# Brakeout_board_-_VEML7700.net
KiCad netlist of a schematic drawn in EAGLE
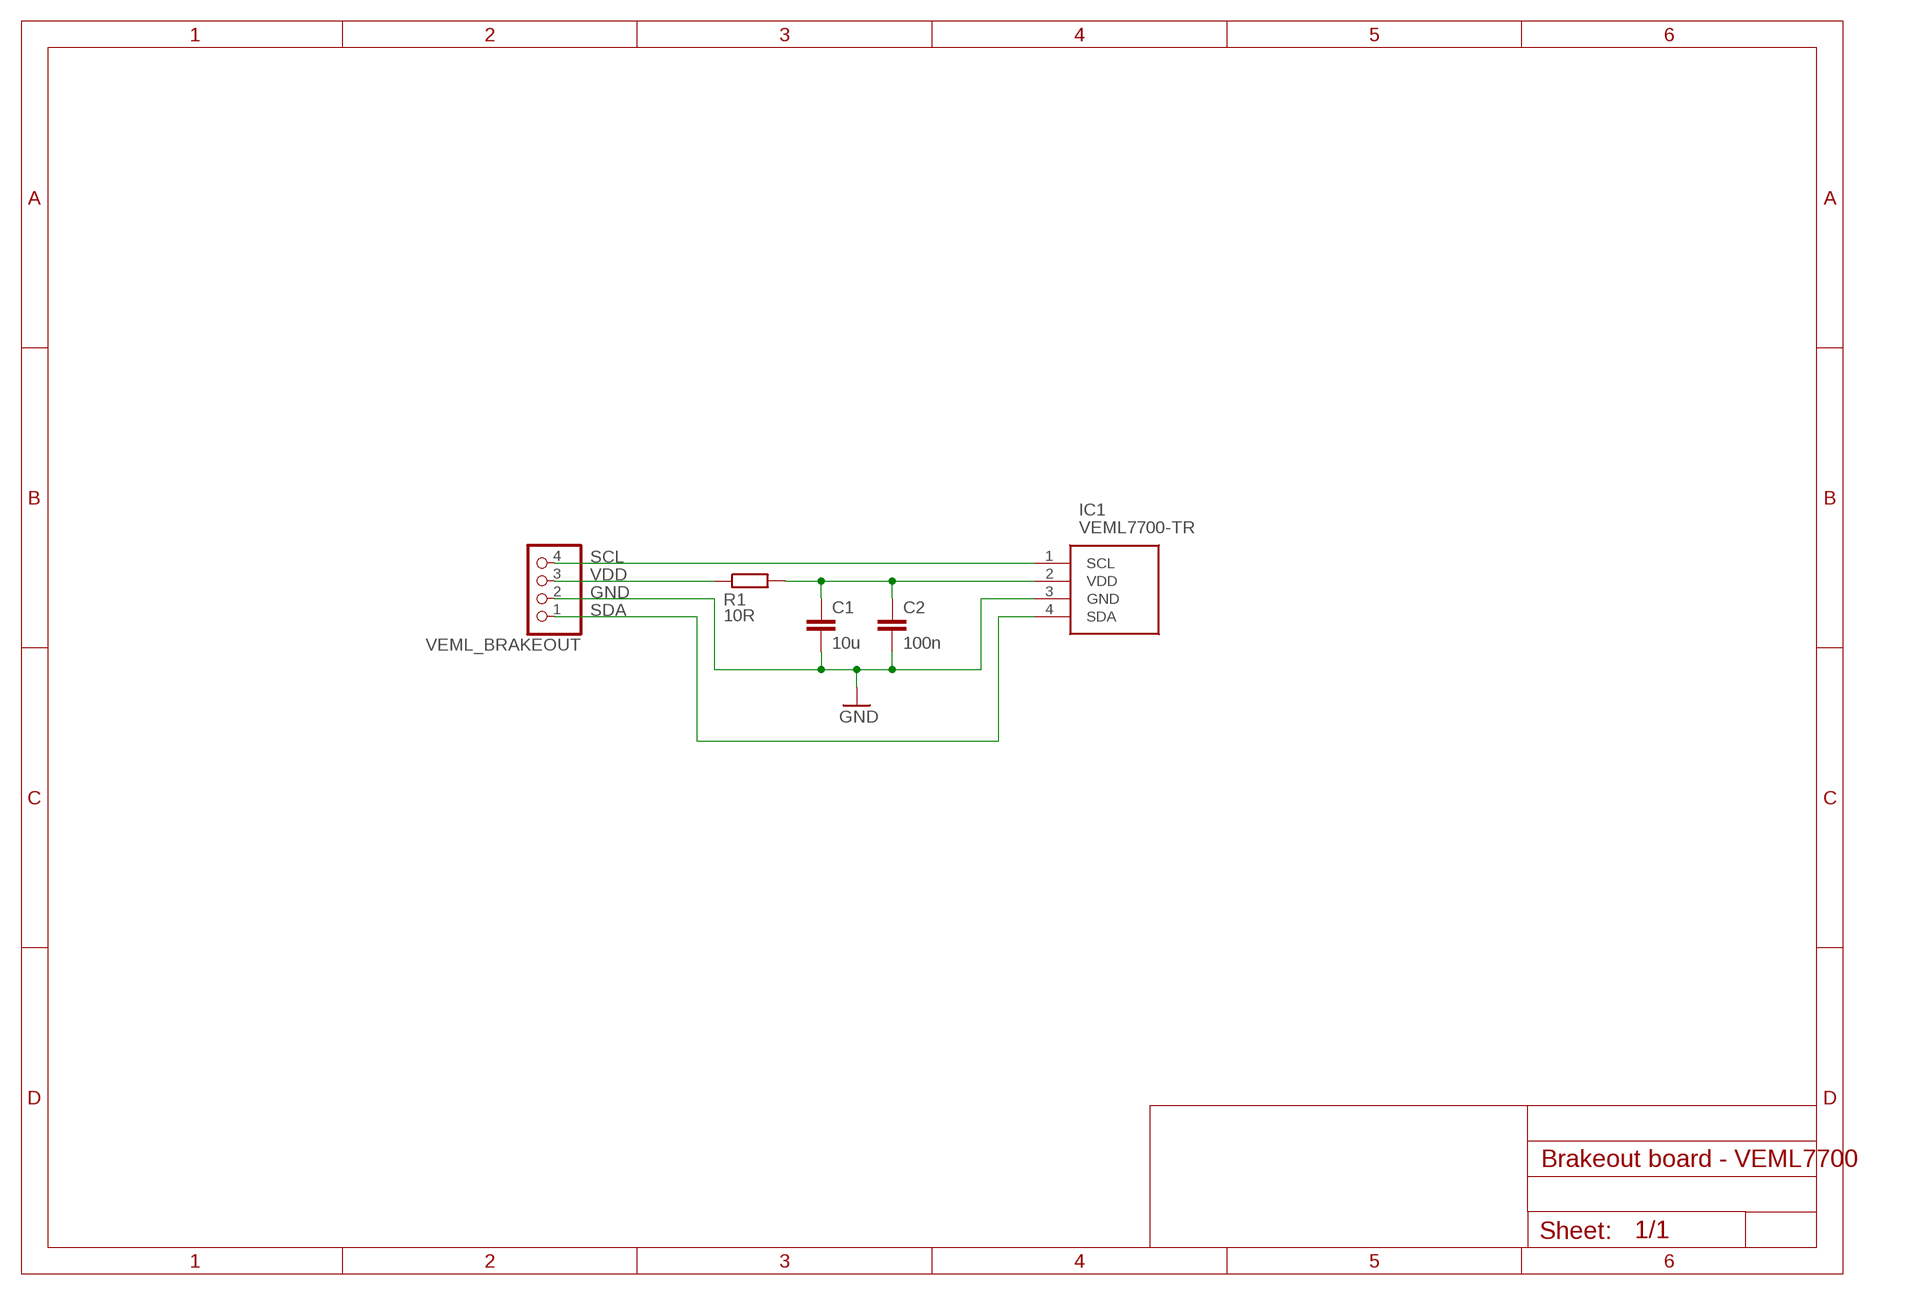
[diagram p0: schematic, sheet 1]

(export (version "E")
  (design (tool "Eeschema 10.0.6"))
  (components
    (comp (ref "C1")
      (value "10u")
      (footprint "eagle-import:C0603")
      (libsource (lib "eagle-import") (part "C-EUC0603"))
    )
    (comp (ref "C2")
      (value "100n")
      (footprint "eagle-import:C0603")
      (libsource (lib "eagle-import") (part "C-EUC0603"))
    )
    (comp (ref "IC1")
      (value "VEML7700-TR")
      (footprint "eagle-import:VEML7700")
      (fields (field (name "MOUSER_PART_NUMBER") "78-VEML7700-TR"))
      (libsource (lib "eagle-import") (part "VEML7700-TR"))
    )
    (comp (ref "R1")
      (value "10R")
      (footprint "eagle-import:R0603")
      (libsource (lib "eagle-import") (part "R-EU_R0603"))
    )
    (comp (ref "VEML_BRAKEOUT")
      (value "PINHD-1X4")
      (footprint "eagle-import:1X04")
      (libsource (lib "eagle-import") (part "PINHD-1X4"))
    )
  )
  (nets
    (net (code "1") (name "/SCL") (class "Default")
      (node (ref "IC1") (pin "1") (pinfunction "SCL_1") (pintype "bidirectional"))
      (node (ref "VEML_BRAKEOUT") (pin "4") (pinfunction "4_4") (pintype "passive"))
    )
    (net (code "2") (name "/SDA") (class "Default")
      (node (ref "IC1") (pin "4") (pinfunction "SDA_4") (pintype "bidirectional"))
      (node (ref "VEML_BRAKEOUT") (pin "1") (pinfunction "1_1") (pintype "passive"))
    )
    (net (code "3") (name "/VDD") (class "Default")
      (node (ref "R1") (pin "1") (pinfunction "1_1") (pintype "passive"))
      (node (ref "VEML_BRAKEOUT") (pin "3") (pinfunction "3_3") (pintype "passive"))
    )
    (net (code "4") (name "GND") (class "Default")
      (node (ref "C1") (pin "2") (pinfunction "2_2") (pintype "passive"))
      (node (ref "C2") (pin "2") (pinfunction "2_2") (pintype "passive"))
      (node (ref "IC1") (pin "3") (pinfunction "GND_3") (pintype "power_in"))
      (node (ref "VEML_BRAKEOUT") (pin "2") (pinfunction "2_2") (pintype "passive"))
    )
    (net (code "5") (name "Net-(IC1-VDD)") (class "Default")
      (node (ref "C1") (pin "1") (pinfunction "1_1") (pintype "passive"))
      (node (ref "C2") (pin "1") (pinfunction "1_1") (pintype "passive"))
      (node (ref "IC1") (pin "2") (pinfunction "VDD_2") (pintype "power_in"))
      (node (ref "R1") (pin "2") (pinfunction "2_2") (pintype "passive"))
    )
  )
)
